# Top_TB.net
KiCad netlist of a schematic drawn in Altium Designer
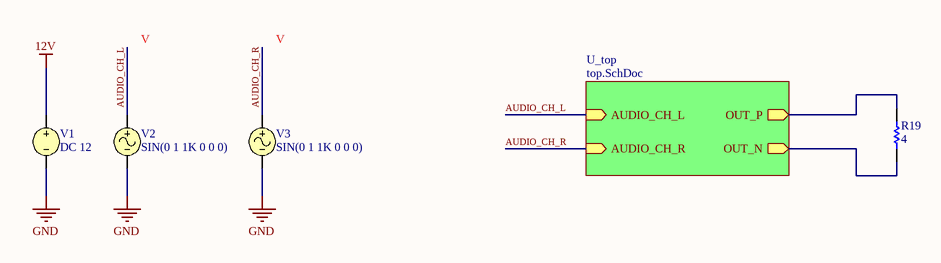
[diagram p0: Top_TB.SchDoc]

(export (version "E")
  (design (tool "Eeschema 10.0.6"))
  (components
    (comp (ref "R19")
      (value "4")
      (description "Resistor")
      (libsource (lib "Simulation Generic Components") (part "Resistor"))
    )
    (comp (ref "V1")
      (value "DC 12")
      (description "Voltage Source")
      (fields (field (name "PUBLISHER") "Altium Limited"))
      (libsource (lib "Simulation Generic Components") (part "VSRC"))
    )
    (comp (ref "V2")
      (value "SIN(0 1 1K 0 0 0)")
      (description "Sinusoidal Voltage Source")
      (fields (field (name "PUBLISHER") "Altium Limited"))
      (libsource (lib "Simulation Generic Components") (part "VSIN"))
    )
    (comp (ref "V3")
      (value "SIN(0 1 1K 0 0 0)")
      (description "Sinusoidal Voltage Source")
      (fields (field (name "PUBLISHER") "Altium Limited"))
      (libsource (lib "Simulation Generic Components") (part "VSIN"))
    )
  )
  (nets
    (net (code "1") (name "/AUDIO_CH_L") (class "Default")
      (node (ref "V2") (pin "1") (pinfunction "1_1") (pintype "passive"))
    )
    (net (code "2") (name "/AUDIO_CH_R") (class "Default")
      (node (ref "V3") (pin "1") (pinfunction "1_1") (pintype "passive"))
    )
    (net (code "3") (name "/OUT_N") (class "Default")
      (node (ref "R19") (pin "1") (pinfunction "1_1") (pintype "passive"))
    )
    (net (code "4") (name "/OUT_P") (class "Default")
      (node (ref "R19") (pin "2") (pinfunction "2_2") (pintype "passive"))
    )
    (net (code "5") (name "12V") (class "Default")
      (node (ref "V1") (pin "1") (pinfunction "1_1") (pintype "passive"))
    )
    (net (code "6") (name "GND") (class "Default")
      (node (ref "V1") (pin "2") (pinfunction "2_2") (pintype "passive"))
      (node (ref "V2") (pin "2") (pinfunction "2_2") (pintype "passive"))
      (node (ref "V3") (pin "2") (pinfunction "2_2") (pintype "passive"))
    )
  )
)
